# MAX3232_Breakout_v11.net
KiCad netlist of a schematic drawn in EAGLE
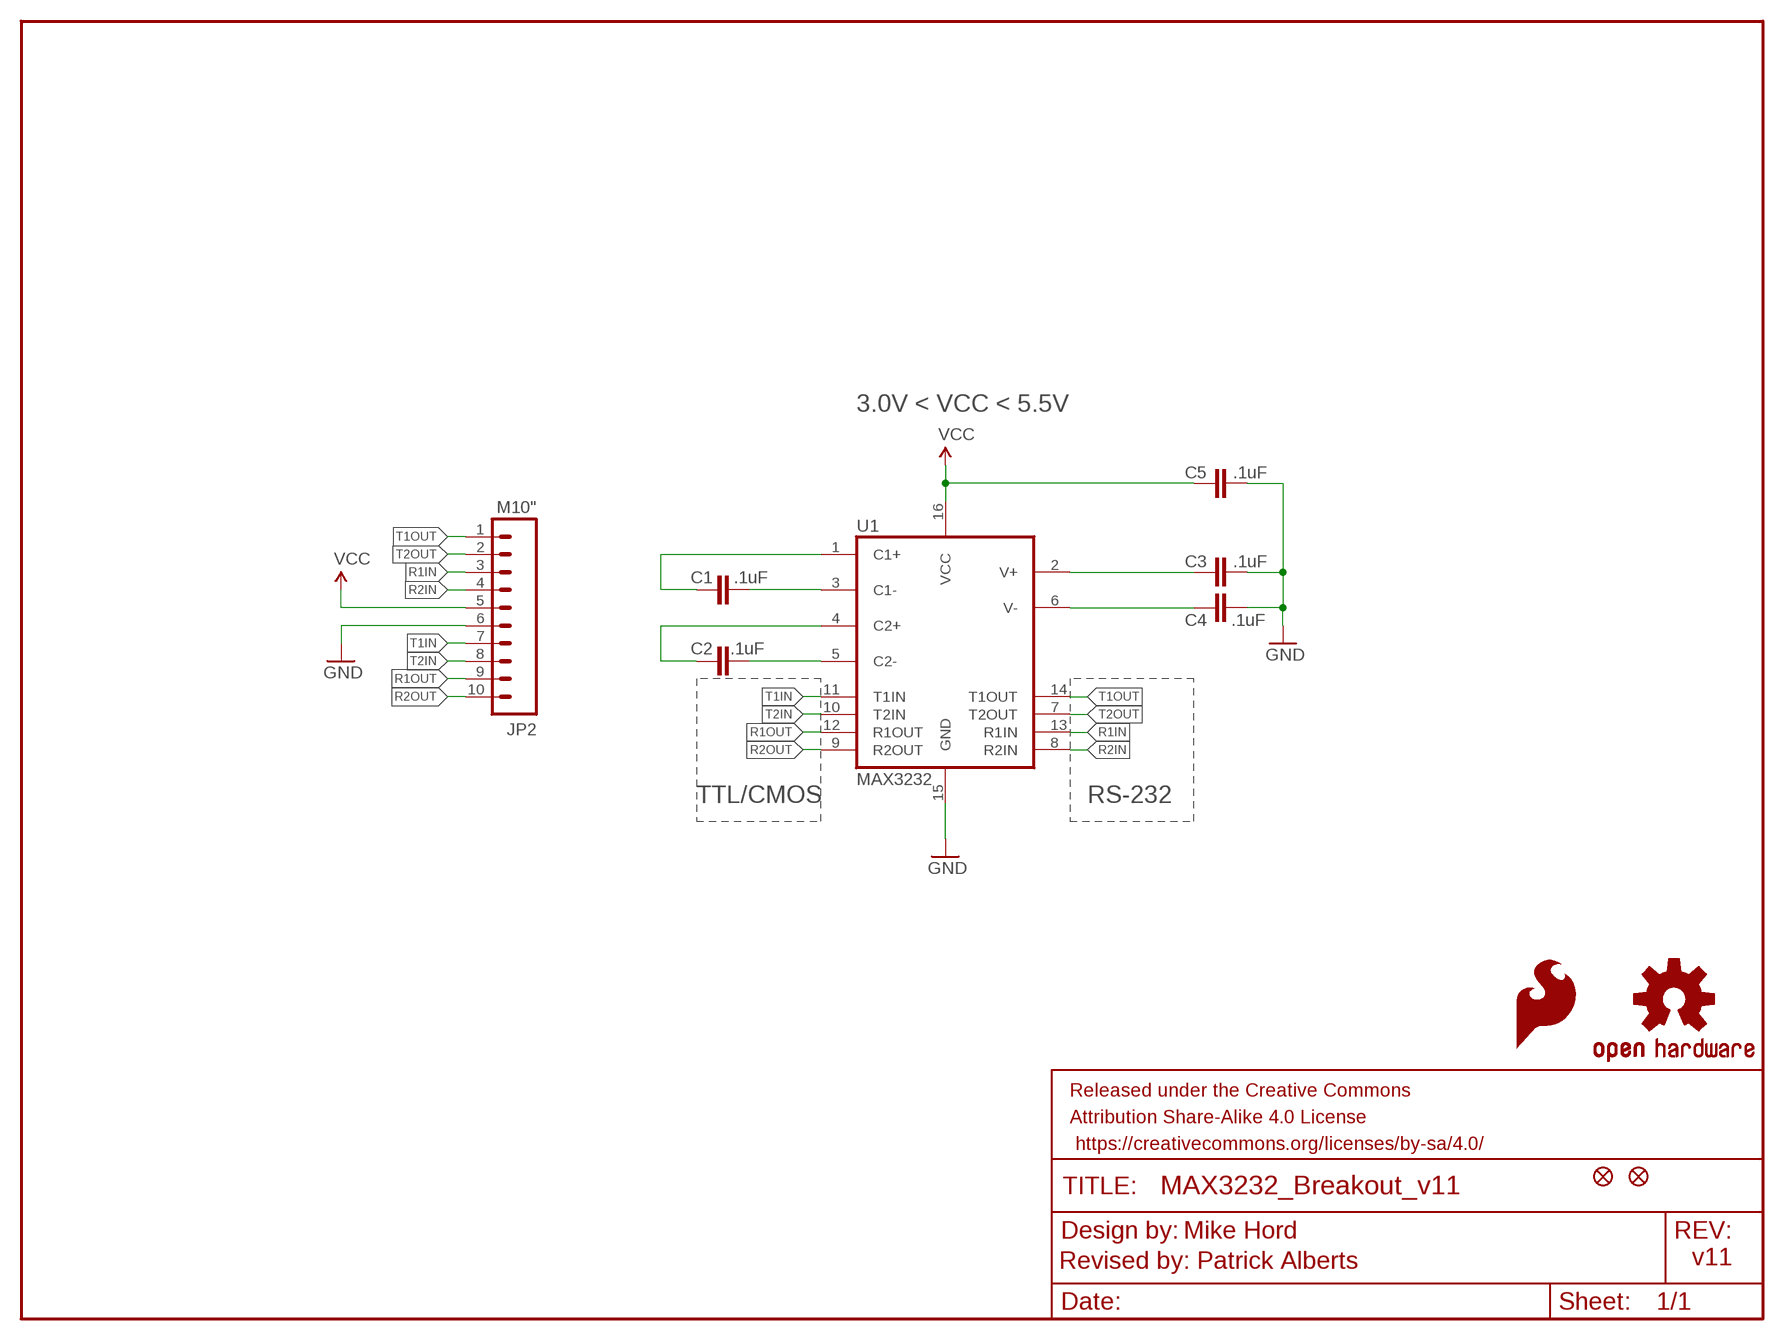
[diagram p0: schematic, sheet 1]

(export (version "E")
  (design (tool "Eeschema 10.0.6"))
  (components
    (comp (ref "C1")
      (value ".1uF")
      (footprint "eagle-import:0603-CAP")
      (fields (field (name "PROD_ID") "CAP-00810"))
      (libsource (lib "eagle-import") (part "0.1UF-25V(+80/-20%)(0603)"))
    )
    (comp (ref "C2")
      (value ".1uF")
      (footprint "eagle-import:0603-CAP")
      (fields (field (name "PROD_ID") "CAP-00810"))
      (libsource (lib "eagle-import") (part "0.1UF-25V(+80/-20%)(0603)"))
    )
    (comp (ref "C3")
      (value ".1uF")
      (footprint "eagle-import:0603-CAP")
      (fields (field (name "PROD_ID") "CAP-00810"))
      (libsource (lib "eagle-import") (part "0.1UF-25V(+80/-20%)(0603)"))
    )
    (comp (ref "C4")
      (value ".1uF")
      (footprint "eagle-import:0603-CAP")
      (fields (field (name "PROD_ID") "CAP-00810"))
      (libsource (lib "eagle-import") (part "0.1UF-25V(+80/-20%)(0603)"))
    )
    (comp (ref "C5")
      (value ".1uF")
      (footprint "eagle-import:0603-CAP")
      (fields (field (name "PROD_ID") "CAP-00810"))
      (libsource (lib "eagle-import") (part "0.1UF-25V(+80/-20%)(0603)"))
    )
    (comp (ref "FID1")
      (value "FIDUCIAL1X2")
      (footprint "eagle-import:FIDUCIAL-1X2")
      (libsource (lib "eagle-import") (part "FIDUCIAL1X2"))
    )
    (comp (ref "FID2")
      (value "FIDUCIAL1X2")
      (footprint "eagle-import:FIDUCIAL-1X2")
      (libsource (lib "eagle-import") (part "FIDUCIAL1X2"))
    )
    (comp (ref "FRAME1")
      (value "FRAME-LETTER")
      (footprint "eagle-import:CREATIVE_COMMONS")
      (fields (field (name "NO_PART") "1") (field (name "DESIGNER") "NAME"))
      (libsource (lib "eagle-import") (part "FRAME-LETTER"))
    )
    (comp (ref "JP2")
      (value "M10\"")
      (footprint "eagle-import:1X10")
      (fields (field (name "NO_PART") "1"))
      (libsource (lib "eagle-import") (part "M10{dblquote}"))
    )
    (comp (ref "LOGO1")
      (value "SFE_LOGO_FLAME.1_INCH")
      (footprint "eagle-import:SFE_LOGO_FLAME_.1")
      (libsource (lib "eagle-import") (part "SFE_LOGO_FLAME.1_INCH"))
    )
    (comp (ref "U$1")
      (value "OSHW-LOGOS")
      (footprint "eagle-import:OSHW-LOGO-S")
      (fields (field (name "NO_PART") "1"))
      (libsource (lib "eagle-import") (part "OSHW-LOGOS"))
    )
    (comp (ref "U1")
      (value "MAX3232")
      (footprint "eagle-import:SO016")
      (libsource (lib "eagle-import") (part "MAX232SOIC16"))
    )
  )
  (nets
    (net (code "1") (name "GND") (class "Default")
      (node (ref "C3") (pin "2") (pinfunction "2_2") (pintype "passive"))
      (node (ref "C4") (pin "2") (pinfunction "2_2") (pintype "passive"))
      (node (ref "C5") (pin "2") (pinfunction "2_2") (pintype "passive"))
      (node (ref "JP2") (pin "6") (pinfunction "6_6") (pintype "passive"))
      (node (ref "U1") (pin "15") (pinfunction "GND_15") (pintype "bidirectional"))
    )
    (net (code "2") (name "Net-(U1-C1+)") (class "Default")
      (node (ref "C1") (pin "1") (pinfunction "1_1") (pintype "passive"))
      (node (ref "U1") (pin "1") (pinfunction "C1+_1") (pintype "bidirectional"))
    )
    (net (code "3") (name "Net-(U1-C1-)") (class "Default")
      (node (ref "C1") (pin "2") (pinfunction "2_2") (pintype "passive"))
      (node (ref "U1") (pin "3") (pinfunction "C1-_3") (pintype "bidirectional"))
    )
    (net (code "4") (name "Net-(U1-C2+)") (class "Default")
      (node (ref "C2") (pin "1") (pinfunction "1_1") (pintype "passive"))
      (node (ref "U1") (pin "4") (pinfunction "C2+_4") (pintype "bidirectional"))
    )
    (net (code "5") (name "Net-(U1-C2-)") (class "Default")
      (node (ref "C2") (pin "2") (pinfunction "2_2") (pintype "passive"))
      (node (ref "U1") (pin "5") (pinfunction "C2-_5") (pintype "bidirectional"))
    )
    (net (code "6") (name "Net-(U1-V+)") (class "Default")
      (node (ref "C3") (pin "1") (pinfunction "1_1") (pintype "passive"))
      (node (ref "U1") (pin "2") (pinfunction "V+_2") (pintype "bidirectional"))
    )
    (net (code "7") (name "Net-(U1-V-)") (class "Default")
      (node (ref "C4") (pin "1") (pinfunction "1_1") (pintype "passive"))
      (node (ref "U1") (pin "6") (pinfunction "V-_6") (pintype "bidirectional"))
    )
    (net (code "8") (name "R1IN") (class "Default")
      (node (ref "JP2") (pin "3") (pinfunction "3_3") (pintype "passive"))
      (node (ref "U1") (pin "13") (pinfunction "R1IN_13") (pintype "input"))
    )
    (net (code "9") (name "R1OUT") (class "Default")
      (node (ref "JP2") (pin "9") (pinfunction "9_9") (pintype "passive"))
      (node (ref "U1") (pin "12") (pinfunction "R1OUT_12") (pintype "output"))
    )
    (net (code "10") (name "R2IN") (class "Default")
      (node (ref "JP2") (pin "4") (pinfunction "4_4") (pintype "passive"))
      (node (ref "U1") (pin "8") (pinfunction "R2IN_8") (pintype "input"))
    )
    (net (code "11") (name "R2OUT") (class "Default")
      (node (ref "JP2") (pin "10") (pinfunction "10_10") (pintype "passive"))
      (node (ref "U1") (pin "9") (pinfunction "R2OUT_9") (pintype "output"))
    )
    (net (code "12") (name "T1IN") (class "Default")
      (node (ref "JP2") (pin "7") (pinfunction "7_7") (pintype "passive"))
      (node (ref "U1") (pin "11") (pinfunction "T1IN_11") (pintype "input"))
    )
    (net (code "13") (name "T1OUT") (class "Default")
      (node (ref "JP2") (pin "1") (pinfunction "1_1") (pintype "passive"))
      (node (ref "U1") (pin "14") (pinfunction "T1OUT_14") (pintype "output"))
    )
    (net (code "14") (name "T2IN") (class "Default")
      (node (ref "JP2") (pin "8") (pinfunction "8_8") (pintype "passive"))
      (node (ref "U1") (pin "10") (pinfunction "T2IN_10") (pintype "input"))
    )
    (net (code "15") (name "T2OUT") (class "Default")
      (node (ref "JP2") (pin "2") (pinfunction "2_2") (pintype "passive"))
      (node (ref "U1") (pin "7") (pinfunction "T2OUT_7") (pintype "output"))
    )
    (net (code "16") (name "VCC") (class "Default")
      (node (ref "C5") (pin "1") (pinfunction "1_1") (pintype "passive"))
      (node (ref "JP2") (pin "5") (pinfunction "5_5") (pintype "passive"))
      (node (ref "U1") (pin "16") (pinfunction "VCC_16") (pintype "bidirectional"))
    )
  )
)
